# Handmouse.net
KiCad netlist of a schematic drawn in Altium Designer
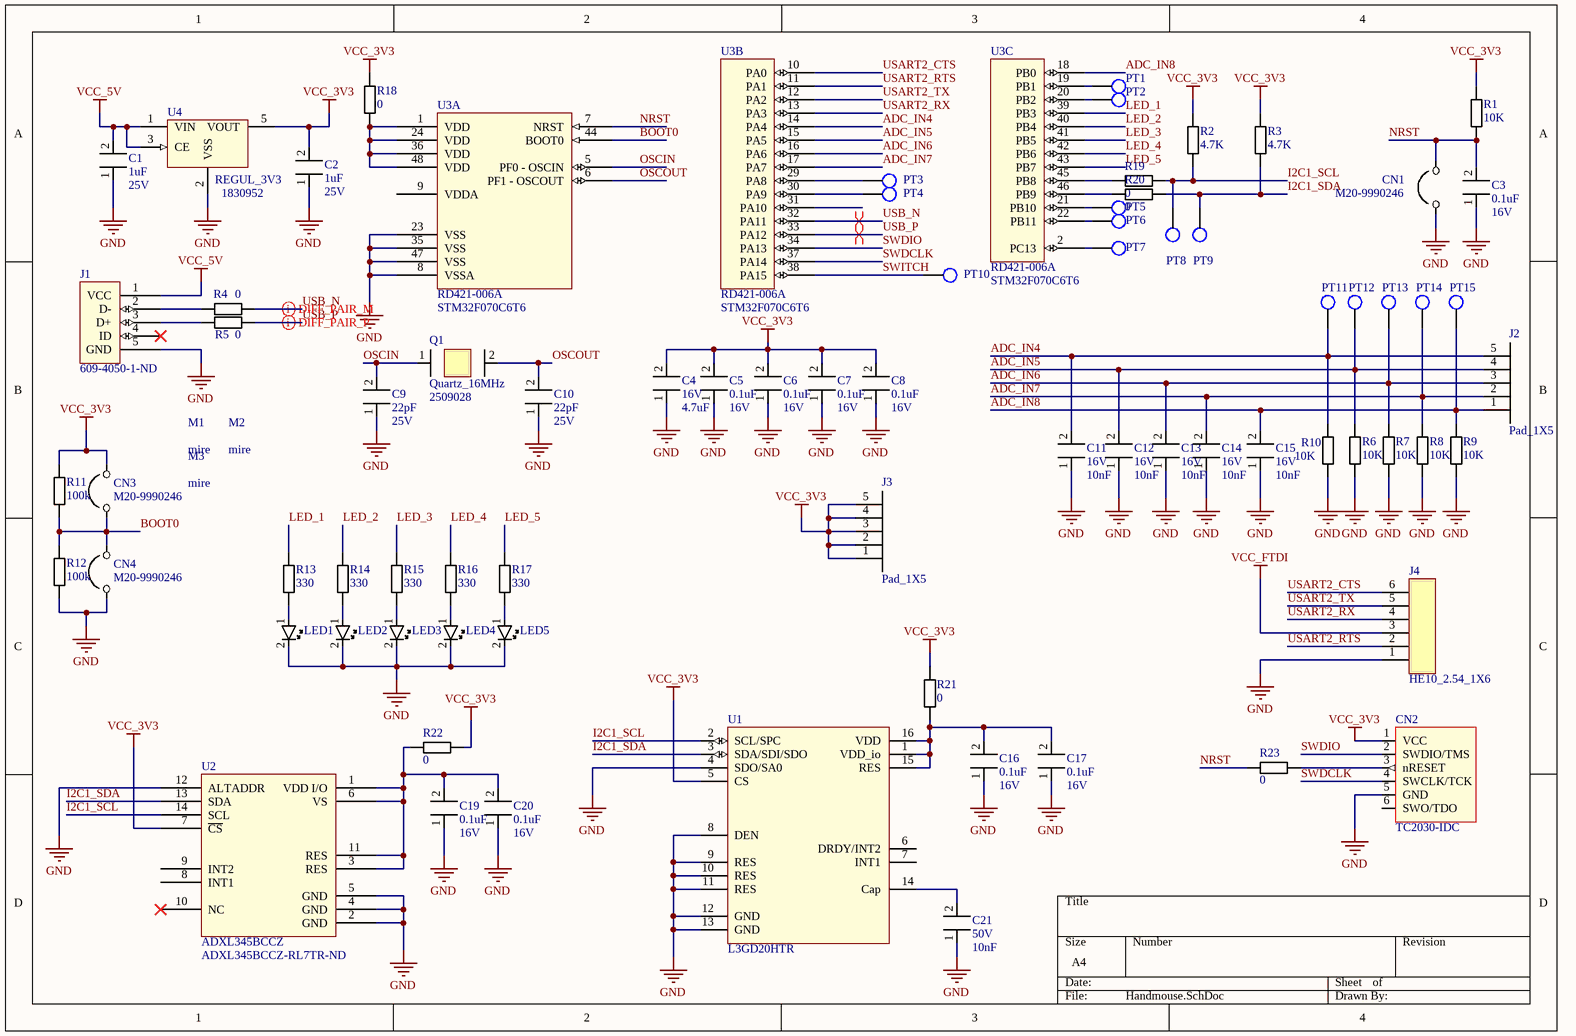
[diagram p0: Handmouse.SchDoc]

(export (version "E")
  (design (tool "Eeschema 10.0.6"))
  (components
    (comp (ref "C1")
      (value "RD401-021A")
      (footprint "0603")
      (description "CAP CER 0603 1uF 25V X7R 10%")
      (fields
        (field (name "MANUFACTURER") "AVX")
        (field (name "MANUFACTURER PART NUMBER") "0603YC105KAT2A")
        (field (name "CAPACITÉ") "1uF")
        (field (name "VOLTAGE") "25V")
      )
      (libsource (lib "Condensateur") (part "RD401-021A"))
    )
    (comp (ref "C2")
      (value "RD401-021A")
      (footprint "0603")
      (description "CAP CER 0603 1uF 25V X7R 10%")
      (fields
        (field (name "MANUFACTURER") "AVX")
        (field (name "MANUFACTURER PART NUMBER") "0603YC105KAT2A")
        (field (name "CAPACITÉ") "1uF")
        (field (name "VOLTAGE") "25V")
      )
      (libsource (lib "Condensateur") (part "RD401-021A"))
    )
    (comp (ref "C3")
      (value "RD401-033A")
      (footprint "0402")
      (description "CAP CER 0402 0.1uF 16V X7R 5%")
      (fields
        (field (name "MANUFACTURER") "KEMET")
        (field (name "MANUFACTURER PART NUMBER") "C0402C104J4RACTU")
        (field (name "CAPACITÉ") "0.1uF")
        (field (name "VOLTAGE") "16V")
      )
      (libsource (lib "Condensateur") (part "RD401-033A"))
    )
    (comp (ref "C4")
      (value "~")
      (footprint "0805")
      (description "CAP CER 0805 4.7uF 16V X7R 10%")
      (fields
        (field (name "MANUFACTURER") "AVX")
        (field (name "MANUFACTURER PART NUMBER") "0805YC475KAT2A")
        (field (name "VOLTAGE") "16V")
        (field (name "CAPACITÉ") "4.7uF")
      )
      (libsource (lib "Condensateur") (part "RD401-025A"))
    )
    (comp (ref "C5")
      (value "RD401-033A")
      (footprint "0402")
      (description "CAP CER 0402 0.1uF 16V X7R 5%")
      (fields
        (field (name "MANUFACTURER") "KEMET")
        (field (name "MANUFACTURER PART NUMBER") "C0402C104J4RACTU")
        (field (name "CAPACITÉ") "0.1uF")
        (field (name "VOLTAGE") "16V")
      )
      (libsource (lib "Condensateur") (part "RD401-033A"))
    )
    (comp (ref "C6")
      (value "RD401-033A")
      (footprint "0402")
      (description "CAP CER 0402 0.1uF 16V X7R 5%")
      (fields
        (field (name "MANUFACTURER") "KEMET")
        (field (name "MANUFACTURER PART NUMBER") "C0402C104J4RACTU")
        (field (name "CAPACITÉ") "0.1uF")
        (field (name "VOLTAGE") "16V")
      )
      (libsource (lib "Condensateur") (part "RD401-033A"))
    )
    (comp (ref "C7")
      (value "RD401-033A")
      (footprint "0402")
      (description "CAP CER 0402 0.1uF 16V X7R 5%")
      (fields
        (field (name "MANUFACTURER") "KEMET")
        (field (name "MANUFACTURER PART NUMBER") "C0402C104J4RACTU")
        (field (name "CAPACITÉ") "0.1uF")
        (field (name "VOLTAGE") "16V")
      )
      (libsource (lib "Condensateur") (part "RD401-033A"))
    )
    (comp (ref "C8")
      (value "RD401-033A")
      (footprint "0402")
      (description "CAP CER 0402 0.1uF 16V X7R 5%")
      (fields
        (field (name "MANUFACTURER") "KEMET")
        (field (name "MANUFACTURER PART NUMBER") "C0402C104J4RACTU")
        (field (name "CAPACITÉ") "0.1uF")
        (field (name "VOLTAGE") "16V")
      )
      (libsource (lib "Condensateur") (part "RD401-033A"))
    )
    (comp (ref "C9")
      (value "22pF")
      (footprint "0402")
      (description "CAP CER 0402 22pF 25V COG 1%")
      (fields (field (name "VOLTAGE") "25V"))
      (libsource (lib "Condensateur") (part "RD401-009A"))
    )
    (comp (ref "C10")
      (value "22pF")
      (footprint "0402")
      (description "CAP CER 0402 22pF 25V COG 1%")
      (fields (field (name "VOLTAGE") "25V"))
      (libsource (lib "Condensateur") (part "RD401-009A"))
    )
    (comp (ref "C11")
      (value "RD401-008A")
      (footprint "0402")
      (description "CAP CER 0402 10nF 16V X7R 5%")
      (fields (field (name "VOLTAGE") "16V") (field (name "CAPACITÉ") "10nF"))
      (libsource (lib "Condensateur") (part "RD401-008A"))
    )
    (comp (ref "C12")
      (value "RD401-008A")
      (footprint "0402")
      (description "CAP CER 0402 10nF 16V X7R 5%")
      (fields (field (name "VOLTAGE") "16V") (field (name "CAPACITÉ") "10nF"))
      (libsource (lib "Condensateur") (part "RD401-008A"))
    )
    (comp (ref "C13")
      (value "RD401-008A")
      (footprint "0402")
      (description "CAP CER 0402 10nF 16V X7R 5%")
      (fields (field (name "VOLTAGE") "16V") (field (name "CAPACITÉ") "10nF"))
      (libsource (lib "Condensateur") (part "RD401-008A"))
    )
    (comp (ref "C14")
      (value "RD401-008A")
      (footprint "0402")
      (description "CAP CER 0402 10nF 16V X7R 5%")
      (fields (field (name "VOLTAGE") "16V") (field (name "CAPACITÉ") "10nF"))
      (libsource (lib "Condensateur") (part "RD401-008A"))
    )
    (comp (ref "C15")
      (value "RD401-008A")
      (footprint "0402")
      (description "CAP CER 0402 10nF 16V X7R 5%")
      (fields (field (name "VOLTAGE") "16V") (field (name "CAPACITÉ") "10nF"))
      (libsource (lib "Condensateur") (part "RD401-008A"))
    )
    (comp (ref "C16")
      (value "RD401-033A")
      (footprint "0402")
      (description "CAP CER 0402 0.1uF 16V X7R 5%")
      (fields
        (field (name "MANUFACTURER") "KEMET")
        (field (name "MANUFACTURER PART NUMBER") "C0402C104J4RACTU")
        (field (name "CAPACITÉ") "0.1uF")
        (field (name "VOLTAGE") "16V")
      )
      (libsource (lib "Condensateur") (part "RD401-033A"))
    )
    (comp (ref "C17")
      (value "RD401-033A")
      (footprint "0402")
      (description "CAP CER 0402 0.1uF 16V X7R 5%")
      (fields
        (field (name "MANUFACTURER") "KEMET")
        (field (name "MANUFACTURER PART NUMBER") "C0402C104J4RACTU")
        (field (name "CAPACITÉ") "0.1uF")
        (field (name "VOLTAGE") "16V")
      )
      (libsource (lib "Condensateur") (part "RD401-033A"))
    )
    (comp (ref "C19")
      (value "RD401-033A")
      (footprint "0402")
      (description "CAP CER 0402 0.1uF 16V X7R 5%")
      (fields
        (field (name "MANUFACTURER") "KEMET")
        (field (name "MANUFACTURER PART NUMBER") "C0402C104J4RACTU")
        (field (name "CAPACITÉ") "0.1uF")
        (field (name "VOLTAGE") "16V")
      )
      (libsource (lib "Condensateur") (part "RD401-033A"))
    )
    (comp (ref "C20")
      (value "RD401-033A")
      (footprint "0402")
      (description "CAP CER 0402 0.1uF 16V X7R 5%")
      (fields
        (field (name "MANUFACTURER") "KEMET")
        (field (name "MANUFACTURER PART NUMBER") "C0402C104J4RACTU")
        (field (name "CAPACITÉ") "0.1uF")
        (field (name "VOLTAGE") "16V")
      )
      (libsource (lib "Condensateur") (part "RD401-033A"))
    )
    (comp (ref "C21")
      (value "RD401-037A")
      (footprint "0402")
      (description "CAP CER 0402 10nF 50V X7R 10%")
      (fields
        (field (name "MANUFACTURER") "KEMET")
        (field (name "MANUFACTURER PART NUMBER") "C0402C103K5RACTU")
        (field (name "VOLTAGE") "50V")
        (field (name "CAPACITE") "10nF")
      )
      (libsource (lib "Condensateur") (part "RD401-037A"))
    )
    (comp (ref "CN1")
      (value "RD408-013A")
      (footprint "PinHead 2*1 M")
      (description "JUMPER")
      (fields (field (name "MANUFACTURER PART NUMBER 1") "M20-9990246"))
      (libsource (lib "Connecteur") (part "RD408-013A"))
    )
    (comp (ref "CN2")
      (value "RD408-022A")
      (footprint "TC2030-IDC-FP")
      (description "CON SWD")
      (fields
        (field (name "MANUFACTURER") "Tag-Connect LLC")
        (field (name "MANUFACTURER PART NUMBER") "TC2030-IDC")
      )
      (libsource (lib "Connecteur") (part "RD408-022A"))
    )
    (comp (ref "CN3")
      (value "RD408-013A")
      (footprint "PinHead 2*1 M")
      (description "JUMPER")
      (fields (field (name "MANUFACTURER PART NUMBER 1") "M20-9990246"))
      (libsource (lib "Connecteur") (part "RD408-013A"))
    )
    (comp (ref "CN4")
      (value "RD408-013A")
      (footprint "PinHead 2*1 M")
      (description "JUMPER")
      (fields (field (name "MANUFACTURER PART NUMBER 1") "M20-9990246"))
      (libsource (lib "Connecteur") (part "RD408-013A"))
    )
    (comp (ref "J1")
      (value "CONN_FCI_10103594-0001LF")
      (footprint "CONN_10103594-0001LF")
      (description "CONN MICROUSB FCI 10103594-0001LF")
      (fields
        (field (name "MANUFACTURER") "Amphenol FCI")
        (field (name "MANUFACTURER PART NUMBER") "10103594-0001LF")
        (field (name "SUPPLIER PART NUMBER 1") "609-4050-1-ND")
      )
      (libsource (lib "Schlib1") (part "CONN_FCI_10103594-0001LF"))
    )
    (comp (ref "J2")
      (value "Pad_1X5")
      (footprint "PCBComponent_1")
      (libsource (lib "Schlib1") (part "Pad_1X5"))
    )
    (comp (ref "J3")
      (value "Pad_1X5")
      (footprint "PCBComponent_1")
      (libsource (lib "Schlib1") (part "Pad_1X5"))
    )
    (comp (ref "J4")
      (value "HE10_2.54_1X6")
      (footprint "PCBComponent_1 - duplicate")
      (libsource (lib "Schlib1") (part "HE10_2.54_1X6"))
    )
    (comp (ref "LED1")
      (value "RD405-006A")
      (footprint "0805")
      (description "DIO LED SMT ? 30mA Rouge")
      (libsource (lib "Diodes") (part "RD405-006A"))
    )
    (comp (ref "LED2")
      (value "RD405-006A")
      (footprint "0805")
      (description "DIO LED SMT ? 30mA Rouge")
      (libsource (lib "Diodes") (part "RD405-006A"))
    )
    (comp (ref "LED3")
      (value "RD405-006A")
      (footprint "0805")
      (description "DIO LED SMT ? 30mA Rouge")
      (libsource (lib "Diodes") (part "RD405-006A"))
    )
    (comp (ref "LED4")
      (value "RD405-006A")
      (footprint "0805")
      (description "DIO LED SMT ? 30mA Rouge")
      (libsource (lib "Diodes") (part "RD405-006A"))
    )
    (comp (ref "LED5")
      (value "RD405-006A")
      (footprint "0805")
      (description "DIO LED SMT ? 30mA Rouge")
      (libsource (lib "Diodes") (part "RD405-006A"))
    )
    (comp (ref "M1")
      (value "mire")
      (footprint "Miscellaneous:Mire")
      (libsource (lib "Miscellaneous") (part "mire"))
    )
    (comp (ref "M2")
      (value "mire")
      (footprint "Miscellaneous:Mire")
      (libsource (lib "Miscellaneous") (part "mire"))
    )
    (comp (ref "M3")
      (value "mire")
      (footprint "Miscellaneous:Mire")
      (libsource (lib "Miscellaneous") (part "mire"))
    )
    (comp (ref "PT1")
      (value "PT 0.8mm")
      (footprint "Pastille_0.8mm")
      (description "Point de test pastille 0.8mm")
      (libsource (lib "Schlib1") (part "PT 0.8mm"))
    )
    (comp (ref "PT2")
      (value "PT 0.8mm")
      (footprint "Pastille_0.8mm")
      (description "Point de test pastille 0.8mm")
      (libsource (lib "Schlib1") (part "PT 0.8mm"))
    )
    (comp (ref "PT3")
      (value "PT 0.8mm")
      (footprint "Pastille_0.8mm")
      (description "Point de test pastille 0.8mm")
      (libsource (lib "Schlib1") (part "PT 0.8mm"))
    )
    (comp (ref "PT4")
      (value "PT 0.8mm")
      (footprint "Pastille_0.8mm")
      (description "Point de test pastille 0.8mm")
      (libsource (lib "Schlib1") (part "PT 0.8mm"))
    )
    (comp (ref "PT5")
      (value "PT 0.8mm")
      (footprint "Pastille_0.8mm")
      (description "Point de test pastille 0.8mm")
      (libsource (lib "Schlib1") (part "PT 0.8mm"))
    )
    (comp (ref "PT6")
      (value "PT 0.8mm")
      (footprint "Pastille_0.8mm")
      (description "Point de test pastille 0.8mm")
      (libsource (lib "Schlib1") (part "PT 0.8mm"))
    )
    (comp (ref "PT7")
      (value "PT 0.8mm")
      (footprint "Pastille_0.8mm")
      (description "Point de test pastille 0.8mm")
      (libsource (lib "Schlib1") (part "PT 0.8mm"))
    )
    (comp (ref "PT8")
      (value "PT 0.8mm")
      (footprint "Pastille_0.8mm")
      (description "Point de test pastille 0.8mm")
      (libsource (lib "Schlib1") (part "PT 0.8mm"))
    )
    (comp (ref "PT9")
      (value "PT 0.8mm")
      (footprint "Pastille_0.8mm")
      (description "Point de test pastille 0.8mm")
      (libsource (lib "Schlib1") (part "PT 0.8mm"))
    )
    (comp (ref "PT10")
      (value "PT 0.8mm")
      (footprint "Pastille_0.8mm")
      (description "Point de test pastille 0.8mm")
      (libsource (lib "Schlib1") (part "PT 0.8mm"))
    )
    (comp (ref "PT11")
      (value "PT 0.8mm")
      (footprint "Pastille_0.8mm")
      (description "Point de test pastille 0.8mm")
      (libsource (lib "Schlib1") (part "PT 0.8mm"))
    )
    (comp (ref "PT12")
      (value "PT 0.8mm")
      (footprint "Pastille_0.8mm")
      (description "Point de test pastille 0.8mm")
      (libsource (lib "Schlib1") (part "PT 0.8mm"))
    )
    (comp (ref "PT13")
      (value "PT 0.8mm")
      (footprint "Pastille_0.8mm")
      (description "Point de test pastille 0.8mm")
      (libsource (lib "Schlib1") (part "PT 0.8mm"))
    )
    (comp (ref "PT14")
      (value "PT 0.8mm")
      (footprint "Pastille_0.8mm")
      (description "Point de test pastille 0.8mm")
      (libsource (lib "Schlib1") (part "PT 0.8mm"))
    )
    (comp (ref "PT15")
      (value "PT 0.8mm")
      (footprint "Pastille_0.8mm")
      (description "Point de test pastille 0.8mm")
      (libsource (lib "Schlib1") (part "PT 0.8mm"))
    )
    (comp (ref "Q1")
      (value "Quartz_16MHz")
      (footprint "PCBComponent_1 - duplicate2")
      (description "Quartz 16MHz")
      (fields
        (field (name "MANUFACTURER") "RALTRON")
        (field (name "MANUFACTURER PART NUMBER") "AS-16.000-18-SMD")
        (field (name "SUPPLIER PART NUMBER 1") "2509028")
      )
      (libsource (lib "Schlib1") (part "Quartz_16MHz"))
    )
    (comp (ref "R1")
      (value "RD403-054A")
      (footprint "0603")
      (description "RES 0603 10K 1% 0.1W")
      (fields
        (field (name "MANUFACTURER") "VISHAY DRALORIC")
        (field (name "MANUFACTURER PART NUMBER") "CRCW060310K0FKEA")
        (field (name "RESISTANCE") "10K")
      )
      (libsource (lib "Resistance") (part "RD403-054A"))
    )
    (comp (ref "R2")
      (value "RD403-046A")
      (footprint "0603")
      (description "RES 0603 4.7K 1% 0.1W")
      (fields
        (field (name "MANUFACTURER") "Vishay Dale")
        (field (name "MANUFACTURER PART NUMBER") "CRCW06034K70FKEA")
        (field (name "RÉSISTANCE (OHMS)") "4.7K")
        (field (name "HAUTEUR") "0,020 po (0,50 mm)")
      )
      (libsource (lib "Resistance") (part "RD403-046A"))
    )
    (comp (ref "R3")
      (value "RD403-046A")
      (footprint "0603")
      (description "RES 0603 4.7K 1% 0.1W")
      (fields
        (field (name "MANUFACTURER") "Vishay Dale")
        (field (name "MANUFACTURER PART NUMBER") "CRCW06034K70FKEA")
        (field (name "RÉSISTANCE (OHMS)") "4.7K")
        (field (name "HAUTEUR") "0,020 po (0,50 mm)")
      )
      (libsource (lib "Resistance") (part "RD403-046A"))
    )
    (comp (ref "R4")
      (value "RD403-044A")
      (footprint "0603")
      (description "RES 0603 0 1% 0.1W")
      (fields
        (field (name "MANUFACTURER") "VISHAY DRALORIC")
        (field (name "MANUFACTURER PART NUMBER") "CRCW06030000Z0EA")
        (field (name "RÉSISTANCE") "0")
      )
      (libsource (lib "Resistance") (part "RD403-044A"))
    )
    (comp (ref "R5")
      (value "RD403-044A")
      (footprint "0603")
      (description "RES 0603 0 1% 0.1W")
      (fields
        (field (name "MANUFACTURER") "VISHAY DRALORIC")
        (field (name "MANUFACTURER PART NUMBER") "CRCW06030000Z0EA")
        (field (name "RÉSISTANCE") "0")
      )
      (libsource (lib "Resistance") (part "RD403-044A"))
    )
    (comp (ref "R6")
      (value "RD403-054A")
      (footprint "0603")
      (description "RES 0603 10K 1% 0.1W")
      (fields
        (field (name "MANUFACTURER") "VISHAY DRALORIC")
        (field (name "MANUFACTURER PART NUMBER") "CRCW060310K0FKEA")
        (field (name "RESISTANCE") "10K")
      )
      (libsource (lib "Resistance") (part "RD403-054A"))
    )
    (comp (ref "R7")
      (value "RD403-054A")
      (footprint "0603")
      (description "RES 0603 10K 1% 0.1W")
      (fields
        (field (name "MANUFACTURER") "VISHAY DRALORIC")
        (field (name "MANUFACTURER PART NUMBER") "CRCW060310K0FKEA")
        (field (name "RESISTANCE") "10K")
      )
      (libsource (lib "Resistance") (part "RD403-054A"))
    )
    (comp (ref "R8")
      (value "RD403-054A")
      (footprint "0603")
      (description "RES 0603 10K 1% 0.1W")
      (fields
        (field (name "MANUFACTURER") "VISHAY DRALORIC")
        (field (name "MANUFACTURER PART NUMBER") "CRCW060310K0FKEA")
        (field (name "RESISTANCE") "10K")
      )
      (libsource (lib "Resistance") (part "RD403-054A"))
    )
    (comp (ref "R9")
      (value "RD403-054A")
      (footprint "0603")
      (description "RES 0603 10K 1% 0.1W")
      (fields
        (field (name "MANUFACTURER") "VISHAY DRALORIC")
        (field (name "MANUFACTURER PART NUMBER") "CRCW060310K0FKEA")
        (field (name "RESISTANCE") "10K")
      )
      (libsource (lib "Resistance") (part "RD403-054A"))
    )
    (comp (ref "R10")
      (value "RD403-054A")
      (footprint "0603")
      (description "RES 0603 10K 1% 0.1W")
      (fields
        (field (name "MANUFACTURER") "VISHAY DRALORIC")
        (field (name "MANUFACTURER PART NUMBER") "CRCW060310K0FKEA")
        (field (name "RESISTANCE") "10K")
      )
      (libsource (lib "Resistance") (part "RD403-054A"))
    )
    (comp (ref "R11")
      (value "100k")
      (footprint "0402")
      (description "RES 0402 100k 1% 0.063W")
      (libsource (lib "Resistance") (part "RD403-007A"))
    )
    (comp (ref "R12")
      (value "100k")
      (footprint "0402")
      (description "RES 0402 100k 1% 0.063W")
      (libsource (lib "Resistance") (part "RD403-007A"))
    )
    (comp (ref "R13")
      (value "330")
      (footprint "0402")
      (description "RES 0402 330 1% 0.063W")
      (libsource (lib "Resistance") (part "RD403-014A"))
    )
    (comp (ref "R14")
      (value "330")
      (footprint "0402")
      (description "RES 0402 330 1% 0.063W")
      (libsource (lib "Resistance") (part "RD403-014A"))
    )
    (comp (ref "R15")
      (value "330")
      (footprint "0402")
      (description "RES 0402 330 1% 0.063W")
      (libsource (lib "Resistance") (part "RD403-014A"))
    )
    (comp (ref "R16")
      (value "330")
      (footprint "0402")
      (description "RES 0402 330 1% 0.063W")
      (libsource (lib "Resistance") (part "RD403-014A"))
    )
    (comp (ref "R17")
      (value "330")
      (footprint "0402")
      (description "RES 0402 330 1% 0.063W")
      (libsource (lib "Resistance") (part "RD403-014A"))
    )
    (comp (ref "R18")
      (value "RD403-044A")
      (footprint "0603")
      (description "RES 0603 0 1% 0.1W")
      (fields
        (field (name "MANUFACTURER") "VISHAY DRALORIC")
        (field (name "MANUFACTURER PART NUMBER") "CRCW06030000Z0EA")
        (field (name "RÉSISTANCE") "0")
      )
      (libsource (lib "Resistance") (part "RD403-044A"))
    )
    (comp (ref "R19")
      (value "RD403-044A")
      (footprint "0603")
      (description "RES 0603 0 1% 0.1W")
      (fields
        (field (name "MANUFACTURER") "VISHAY DRALORIC")
        (field (name "MANUFACTURER PART NUMBER") "CRCW06030000Z0EA")
        (field (name "RÉSISTANCE") "0")
      )
      (libsource (lib "Resistance") (part "RD403-044A"))
    )
    (comp (ref "R20")
      (value "RD403-044A")
      (footprint "0603")
      (description "RES 0603 0 1% 0.1W")
      (fields
        (field (name "MANUFACTURER") "VISHAY DRALORIC")
        (field (name "MANUFACTURER PART NUMBER") "CRCW06030000Z0EA")
        (field (name "RÉSISTANCE") "0")
      )
      (libsource (lib "Resistance") (part "RD403-044A"))
    )
    (comp (ref "R21")
      (value "RD403-044A")
      (footprint "0603")
      (description "RES 0603 0 1% 0.1W")
      (fields
        (field (name "MANUFACTURER") "VISHAY DRALORIC")
        (field (name "MANUFACTURER PART NUMBER") "CRCW06030000Z0EA")
        (field (name "RÉSISTANCE") "0")
      )
      (libsource (lib "Resistance") (part "RD403-044A"))
    )
    (comp (ref "R22")
      (value "RD403-044A")
      (footprint "0603")
      (description "RES 0603 0 1% 0.1W")
      (fields
        (field (name "MANUFACTURER") "VISHAY DRALORIC")
        (field (name "MANUFACTURER PART NUMBER") "CRCW06030000Z0EA")
        (field (name "RÉSISTANCE") "0")
      )
      (libsource (lib "Resistance") (part "RD403-044A"))
    )
    (comp (ref "R23")
      (value "RD403-044A")
      (footprint "0603")
      (description "RES 0603 0 1% 0.1W")
      (fields
        (field (name "MANUFACTURER") "VISHAY DRALORIC")
        (field (name "MANUFACTURER PART NUMBER") "CRCW06030000Z0EA")
        (field (name "RÉSISTANCE") "0")
      )
      (libsource (lib "Resistance") (part "RD403-044A"))
    )
    (comp (ref "U1")
      (value "RD498-005A")
      (footprint "LGA_50P_300X300_16")
      (description "Gyroscopes MEMS motion sensor 3axis digital output")
      (fields (field (name "MANUFACTURER PART NUMBER 1") "L3GD20HTR") (field (name "HAUTEUR") "1 mm"))
      (libsource (lib "Miscellaneous") (part "RD498-005A"))
    )
    (comp (ref "U2")
      (value "ADXL345BCCZ")
      (footprint "PCBComponent_1 - duplicate1")
      (fields
        (field (name "MANUFACTURER") "Analog Devices Inc.")
        (field (name "MANUFACTURER PART NUMBER") "ADXL345BCCZ-RL7")
        (field (name "SUPPLIER PART NUMBER 1") "ADXL345BCCZ-RL7TR-ND")
      )
      (libsource (lib "Schlib1") (part "ADXL345BCCZ"))
    )
    (comp (ref "U3")
      (value "RD421-006A")
      (footprint "LQFP48")
      (description "STM32F070C6T6")
      (fields
        (field (name "MANUFACTURER") "STMICROELECTRONICS")
        (field (name "MANUFACTURER PART NUMBER") "STM32F070C6T6")
      )
      (libsource (lib "SOC") (part "RD421-006A"))
    )
    (comp (ref "U4")
      (value "REGUL_3V3")
      (footprint "SOIC95P280X130-5")
      (fields
        (field (name "MANUFACTURER") "TOREX")
        (field (name "MANUFACTURER PART NUMBER") "XC6222D331MR-G")
        (field (name "SUPPLIER PART NUMBER 1") "1830952")
      )
      (libsource (lib "Schlib1") (part "REGUL_3V3"))
    )
  )
  (nets
    (net (code "1") (name "/ADC_IN4") (class "Default")
      (node (ref "C11") (pin "2") (pinfunction "2_2") (pintype "passive"))
      (node (ref "J2") (pin "5") (pinfunction "5_5") (pintype "passive"))
      (node (ref "PT11") (pin "1") (pinfunction "1_1") (pintype "passive"))
      (node (ref "R10") (pin "2") (pinfunction "4_2") (pintype "passive"))
      (node (ref "U3") (pin "14") (pinfunction "PA4_14") (pintype "bidirectional"))
    )
    (net (code "2") (name "/ADC_IN5") (class "Default")
      (node (ref "C12") (pin "2") (pinfunction "2_2") (pintype "passive"))
      (node (ref "J2") (pin "4") (pinfunction "4_4") (pintype "passive"))
      (node (ref "PT12") (pin "1") (pinfunction "1_1") (pintype "passive"))
      (node (ref "R6") (pin "2") (pinfunction "4_2") (pintype "passive"))
      (node (ref "U3") (pin "15") (pinfunction "PA5_15") (pintype "bidirectional"))
    )
    (net (code "3") (name "/ADC_IN6") (class "Default")
      (node (ref "C13") (pin "2") (pinfunction "2_2") (pintype "passive"))
      (node (ref "J2") (pin "3") (pinfunction "3_3") (pintype "passive"))
      (node (ref "PT13") (pin "1") (pinfunction "1_1") (pintype "passive"))
      (node (ref "R7") (pin "2") (pinfunction "4_2") (pintype "passive"))
      (node (ref "U3") (pin "16") (pinfunction "PA6_16") (pintype "bidirectional"))
    )
    (net (code "4") (name "/ADC_IN7") (class "Default")
      (node (ref "C14") (pin "2") (pinfunction "2_2") (pintype "passive"))
      (node (ref "J2") (pin "2") (pinfunction "2_2") (pintype "passive"))
      (node (ref "PT14") (pin "1") (pinfunction "1_1") (pintype "passive"))
      (node (ref "R8") (pin "2") (pinfunction "4_2") (pintype "passive"))
      (node (ref "U3") (pin "17") (pinfunction "PA7_17") (pintype "bidirectional"))
    )
    (net (code "5") (name "/ADC_IN8") (class "Default")
      (node (ref "C15") (pin "2") (pinfunction "2_2") (pintype "passive"))
      (node (ref "J2") (pin "1") (pinfunction "1_1") (pintype "passive"))
      (node (ref "PT15") (pin "1") (pinfunction "1_1") (pintype "passive"))
      (node (ref "R9") (pin "2") (pinfunction "4_2") (pintype "passive"))
      (node (ref "U3") (pin "18") (pinfunction "PB0_18") (pintype "bidirectional"))
    )
    (net (code "6") (name "/BOOT0") (class "Default")
      (node (ref "CN3") (pin "1") (pinfunction "1_1") (pintype "power_in"))
      (node (ref "CN4") (pin "2") (pinfunction "2_2") (pintype "power_in"))
      (node (ref "R11") (pin "1") (pinfunction "3_1") (pintype "passive"))
      (node (ref "R12") (pin "2") (pinfunction "4_2") (pintype "passive"))
      (node (ref "U3") (pin "44") (pinfunction "BOOT0_44") (pintype "input"))
    )
    (net (code "7") (name "/I2C1_SCL") (class "Default")
      (node (ref "PT8") (pin "1") (pinfunction "1_1") (pintype "passive"))
      (node (ref "R19") (pin "2") (pinfunction "4_2") (pintype "passive"))
      (node (ref "R2") (pin "1") (pinfunction "3_1") (pintype "passive"))
      (node (ref "U1") (pin "2") (pinfunction "SCL/SPC_2") (pintype "bidirectional"))
      (node (ref "U2") (pin "14") (pinfunction "SCL_14") (pintype "passive"))
    )
    (net (code "8") (name "/I2C1_SDA") (class "Default")
      (node (ref "PT9") (pin "1") (pinfunction "1_1") (pintype "passive"))
      (node (ref "R20") (pin "2") (pinfunction "4_2") (pintype "passive"))
      (node (ref "R3") (pin "1") (pinfunction "3_1") (pintype "passive"))
      (node (ref "U1") (pin "3") (pinfunction "SDA/SDI/SDO_3") (pintype "bidirectional"))
      (node (ref "U2") (pin "13") (pinfunction "SDA_13") (pintype "passive"))
    )
    (net (code "9") (name "/LED_1") (class "Default")
      (node (ref "R13") (pin "2") (pinfunction "4_2") (pintype "passive"))
      (node (ref "U3") (pin "39") (pinfunction "PB3_39") (pintype "bidirectional"))
    )
    (net (code "10") (name "/LED_2") (class "Default")
      (node (ref "R14") (pin "2") (pinfunction "4_2") (pintype "passive"))
      (node (ref "U3") (pin "40") (pinfunction "PB4_40") (pintype "bidirectional"))
    )
    (net (code "11") (name "/LED_3") (class "Default")
      (node (ref "R15") (pin "2") (pinfunction "4_2") (pintype "passive"))
      (node (ref "U3") (pin "41") (pinfunction "PB5_41") (pintype "bidirectional"))
    )
    (net (code "12") (name "/LED_4") (class "Default")
      (node (ref "R16") (pin "2") (pinfunction "4_2") (pintype "passive"))
      (node (ref "U3") (pin "42") (pinfunction "PB6_42") (pintype "bidirectional"))
    )
    (net (code "13") (name "/LED_5") (class "Default")
      (node (ref "R17") (pin "2") (pinfunction "4_2") (pintype "passive"))
      (node (ref "U3") (pin "43") (pinfunction "PB7_43") (pintype "bidirectional"))
    )
    (net (code "14") (name "/NRST") (class "Default")
      (node (ref "C3") (pin "2") (pinfunction "2_2") (pintype "passive"))
      (node (ref "CN1") (pin "2") (pinfunction "2_2") (pintype "power_in"))
      (node (ref "R1") (pin "1") (pinfunction "3_1") (pintype "passive"))
      (node (ref "R23") (pin "2") (pinfunction "4_2") (pintype "passive"))
      (node (ref "U3") (pin "7") (pinfunction "NRST_7") (pintype "input"))
    )
    (net (code "15") (name "/OSCIN") (class "Default")
      (node (ref "C9") (pin "2") (pinfunction "2_2") (pintype "passive"))
      (node (ref "Q1") (pin "1") (pinfunction "1_1") (pintype "passive"))
      (node (ref "U3") (pin "5") (pinfunction "PF0_-_OSCIN_5") (pintype "bidirectional"))
    )
    (net (code "16") (name "/OSCOUT") (class "Default")
      (node (ref "C10") (pin "2") (pinfunction "2_2") (pintype "passive"))
      (node (ref "Q1") (pin "2") (pinfunction "2_2") (pintype "passive"))
      (node (ref "U3") (pin "6") (pinfunction "PF1_-_OSCOUT_6") (pintype "bidirectional"))
    )
    (net (code "17") (name "/SWDCLK") (class "Default")
      (node (ref "CN2") (pin "4") (pinfunction "SWCLK/TCK_4") (pintype "bidirectional"))
      (node (ref "U3") (pin "37") (pinfunction "PA14_37") (pintype "bidirectional"))
    )
    (net (code "18") (name "/SWDIO") (class "Default")
      (node (ref "CN2") (pin "2") (pinfunction "SWDIO/TMS_2") (pintype "bidirectional"))
      (node (ref "U3") (pin "34") (pinfunction "PA13_34") (pintype "bidirectional"))
    )
    (net (code "19") (name "/SWITCH") (class "Default")
      (node (ref "PT10") (pin "1") (pinfunction "1_1") (pintype "passive"))
      (node (ref "U3") (pin "38") (pinfunction "PA15_38") (pintype "bidirectional"))
    )
    (net (code "20") (name "/USART2_CTS") (class "Default")
      (node (ref "J4") (pin "6") (pinfunction "6_6") (pintype "passive"))
      (node (ref "U3") (pin "10") (pinfunction "PA0_10") (pintype "bidirectional"))
    )
    (net (code "21") (name "/USART2_RTS") (class "Default")
      (node (ref "J4") (pin "2") (pinfunction "2_2") (pintype "passive"))
      (node (ref "U3") (pin "11") (pinfunction "PA1_11") (pintype "bidirectional"))
    )
    (net (code "22") (name "/USART2_RX") (class "Default")
      (node (ref "J4") (pin "4") (pinfunction "4_4") (pintype "passive"))
      (node (ref "U3") (pin "13") (pinfunction "PA3_13") (pintype "bidirectional"))
    )
    (net (code "23") (name "/USART2_TX") (class "Default")
      (node (ref "J4") (pin "5") (pinfunction "5_5") (pintype "passive"))
      (node (ref "U3") (pin "12") (pinfunction "PA2_12") (pintype "bidirectional"))
    )
    (net (code "24") (name "/USB_N") (class "Default")
      (node (ref "R4") (pin "2") (pinfunction "4_2") (pintype "passive"))
      (node (ref "U3") (pin "32") (pinfunction "PA11_32") (pintype "bidirectional"))
    )
    (net (code "25") (name "/USB_P") (class "Default")
      (node (ref "R5") (pin "2") (pinfunction "4_2") (pintype "passive"))
      (node (ref "U3") (pin "33") (pinfunction "PA12_33") (pintype "bidirectional"))
    )
    (net (code "26") (name "GND") (class "Default")
      (node (ref "C1") (pin "1") (pinfunction "1_1") (pintype "passive"))
      (node (ref "C10") (pin "1") (pinfunction "1_1") (pintype "passive"))
      (node (ref "C11") (pin "1") (pinfunction "1_1") (pintype "passive"))
      (node (ref "C12") (pin "1") (pinfunction "1_1") (pintype "passive"))
      (node (ref "C13") (pin "1") (pinfunction "1_1") (pintype "passive"))
      (node (ref "C14") (pin "1") (pinfunction "1_1") (pintype "passive"))
      (node (ref "C15") (pin "1") (pinfunction "1_1") (pintype "passive"))
      (node (ref "C16") (pin "1") (pinfunction "1_1") (pintype "passive"))
      (node (ref "C17") (pin "1") (pinfunction "1_1") (pintype "passive"))
      (node (ref "C19") (pin "1") (pinfunction "1_1") (pintype "passive"))
      (node (ref "C2") (pin "1") (pinfunction "1_1") (pintype "passive"))
      (node (ref "C20") (pin "1") (pinfunction "1_1") (pintype "passive"))
      (node (ref "C21") (pin "1") (pinfunction "1_1") (pintype "passive"))
      (node (ref "C3") (pin "1") (pinfunction "1_1") (pintype "passive"))
      (node (ref "C4") (pin "1") (pinfunction "1_1") (pintype "passive"))
      (node (ref "C5") (pin "1") (pinfunction "1_1") (pintype "passive"))
      (node (ref "C6") (pin "1") (pinfunction "1_1") (pintype "passive"))
      (node (ref "C7") (pin "1") (pinfunction "1_1") (pintype "passive"))
      (node (ref "C8") (pin "1") (pinfunction "1_1") (pintype "passive"))
      (node (ref "C9") (pin "1") (pinfunction "1_1") (pintype "passive"))
      (node (ref "CN1") (pin "1") (pinfunction "1_1") (pintype "power_in"))
      (node (ref "CN2") (pin "5") (pinfunction "GND_5") (pintype "power_in"))
      (node (ref "CN4") (pin "1") (pinfunction "1_1") (pintype "power_in"))
      (node (ref "J1") (pin "5") (pinfunction "GND_5") (pintype "power_in"))
      (node (ref "J4") (pin "1") (pinfunction "1_1") (pintype "passive"))
      (node (ref "LED1") (pin "2") (pinfunction "2_2") (pintype "passive"))
      (node (ref "LED2") (pin "2") (pinfunction "2_2") (pintype "passive"))
      (node (ref "LED3") (pin "2") (pinfunction "2_2") (pintype "passive"))
      (node (ref "LED4") (pin "2") (pinfunction "2_2") (pintype "passive"))
      (node (ref "LED5") (pin "2") (pinfunction "2_2") (pintype "passive"))
      (node (ref "R10") (pin "1") (pinfunction "3_1") (pintype "passive"))
      (node (ref "R12") (pin "1") (pinfunction "3_1") (pintype "passive"))
      (node (ref "R6") (pin "1") (pinfunction "3_1") (pintype "passive"))
      (node (ref "R7") (pin "1") (pinfunction "3_1") (pintype "passive"))
      (node (ref "R8") (pin "1") (pinfunction "3_1") (pintype "passive"))
      (node (ref "R9") (pin "1") (pinfunction "3_1") (pintype "passive"))
      (node (ref "U1") (pin "10") (pinfunction "RES_10") (pintype "passive"))
      (node (ref "U1") (pin "11") (pinfunction "RES_11") (pintype "passive"))
      (node (ref "U1") (pin "12") (pinfunction "GND_12") (pintype "power_in"))
      (node (ref "U1") (pin "13") (pinfunction "GND_13") (pintype "power_in"))
      (node (ref "U1") (pin "4") (pinfunction "SDO/SA0_4") (pintype "passive"))
      (node (ref "U1") (pin "8") (pinfunction "DEN_8") (pintype "passive"))
      (node (ref "U1") (pin "9") (pinfunction "RES_9") (pintype "passive"))
      (node (ref "U2") (pin "12") (pinfunction "ALTADDR_12") (pintype "passive"))
      (node (ref "U2") (pin "2") (pinfunction "GND_2") (pintype "power_in"))
      (node (ref "U2") (pin "4") (pinfunction "GND_4") (pintype "power_in"))
      (node (ref "U2") (pin "5") (pinfunction "GND_5") (pintype "power_in"))
      (node (ref "U3") (pin "23") (pinfunction "VSS_23") (pintype "power_in"))
      (node (ref "U3") (pin "35") (pinfunction "VSS_35") (pintype "power_in"))
      (node (ref "U3") (pin "47") (pinfunction "VSS_47") (pintype "power_in"))
      (node (ref "U3") (pin "8") (pinfunction "VSSA_8") (pintype "power_in"))
      (node (ref "U4") (pin "2") (pinfunction "VSS_2") (pintype "power_in"))
    )
    (net (code "27") (name "Net-(CN2-nRESET)") (class "Default")
      (node (ref "CN2") (pin "3") (pinfunction "nRESET_3") (pintype "output"))
      (node (ref "R23") (pin "1") (pinfunction "3_1") (pintype "passive"))
    )
    (net (code "28") (name "Net-(J1-D+)") (class "Default")
      (node (ref "J1") (pin "3") (pinfunction "D+_3") (pintype "bidirectional"))
      (node (ref "R5") (pin "1") (pinfunction "3_1") (pintype "passive"))
    )
    (net (code "29") (name "Net-(J1-D-)") (class "Default")
      (node (ref "J1") (pin "2") (pinfunction "D-_2") (pintype "bidirectional"))
      (node (ref "R4") (pin "1") (pinfunction "3_1") (pintype "passive"))
    )
    (net (code "30") (name "Net-(R13-3)") (class "Default")
      (node (ref "LED1") (pin "1") (pinfunction "1_1") (pintype "passive"))
      (node (ref "R13") (pin "1") (pinfunction "3_1") (pintype "passive"))
    )
    (net (code "31") (name "Net-(R14-3)") (class "Default")
      (node (ref "LED2") (pin "1") (pinfunction "1_1") (pintype "passive"))
      (node (ref "R14") (pin "1") (pinfunction "3_1") (pintype "passive"))
    )
    (net (code "32") (name "Net-(R15-3)") (class "Default")
      (node (ref "LED3") (pin "1") (pinfunction "1_1") (pintype "passive"))
      (node (ref "R15") (pin "1") (pinfunction "3_1") (pintype "passive"))
    )
    (net (code "33") (name "Net-(R16-3)") (class "Default")
      (node (ref "LED4") (pin "1") (pinfunction "1_1") (pintype "passive"))
      (node (ref "R16") (pin "1") (pinfunction "3_1") (pintype "passive"))
    )
    (net (code "34") (name "Net-(R17-3)") (class "Default")
      (node (ref "LED5") (pin "1") (pinfunction "1_1") (pintype "passive"))
      (node (ref "R17") (pin "1") (pinfunction "3_1") (pintype "passive"))
    )
    (net (code "35") (name "Net-(R18-3)") (class "Default")
      (node (ref "R18") (pin "1") (pinfunction "3_1") (pintype "passive"))
      (node (ref "U3") (pin "1") (pinfunction "VDD_1") (pintype "passive"))
      (node (ref "U3") (pin "24") (pinfunction "VDD_24") (pintype "power_in"))
      (node (ref "U3") (pin "36") (pinfunction "VDD_36") (pintype "power_in"))
      (node (ref "U3") (pin "48") (pinfunction "VDD_48") (pintype "power_in"))
    )
    (net (code "36") (name "Net-(R19-3)") (class "Default")
      (node (ref "R19") (pin "1") (pinfunction "3_1") (pintype "passive"))
      (node (ref "U3") (pin "45") (pinfunction "PB8_45") (pintype "bidirectional"))
    )
    (net (code "37") (name "Net-(R20-3)") (class "Default")
      (node (ref "R20") (pin "1") (pinfunction "3_1") (pintype "passive"))
      (node (ref "U3") (pin "46") (pinfunction "PB9_46") (pintype "bidirectional"))
    )
    (net (code "38") (name "Net-(R21-3)") (class "Default")
      (node (ref "C16") (pin "2") (pinfunction "2_2") (pintype "passive"))
      (node (ref "C17") (pin "2") (pinfunction "2_2") (pintype "passive"))
      (node (ref "R21") (pin "1") (pinfunction "3_1") (pintype "passive"))
      (node (ref "U1") (pin "1") (pinfunction "VDD_io_1") (pintype "power_in"))
      (node (ref "U1") (pin "15") (pinfunction "RES_15") (pintype "passive"))
      (node (ref "U1") (pin "16") (pinfunction "VDD_16") (pintype "power_in"))
    )
    (net (code "39") (name "Net-(R22-3)") (class "Default")
      (node (ref "C19") (pin "2") (pinfunction "2_2") (pintype "passive"))
      (node (ref "C20") (pin "2") (pinfunction "2_2") (pintype "passive"))
      (node (ref "R22") (pin "1") (pinfunction "3_1") (pintype "passive"))
      (node (ref "U2") (pin "1") (pinfunction "VDD_I/O_1") (pintype "power_in"))
      (node (ref "U2") (pin "11") (pinfunction "RES_11") (pintype "passive"))
      (node (ref "U2") (pin "3") (pinfunction "RES_3") (pintype "power_in"))
      (node (ref "U2") (pin "6") (pinfunction "VS_6") (pintype "power_in"))
    )
    (net (code "40") (name "Net-(U1-Cap)") (class "Default")
      (node (ref "C21") (pin "2") (pinfunction "2_2") (pintype "passive"))
      (node (ref "U1") (pin "14") (pinfunction "Cap_14") (pintype "passive"))
    )
    (net (code "41") (name "Net-(U3B-PA8)") (class "Default")
      (node (ref "PT3") (pin "1") (pinfunction "1_1") (pintype "passive"))
      (node (ref "U3") (pin "29") (pinfunction "PA8_29") (pintype "bidirectional"))
    )
    (net (code "42") (name "Net-(U3B-PA9)") (class "Default")
      (node (ref "PT4") (pin "1") (pinfunction "1_1") (pintype "passive"))
      (node (ref "U3") (pin "30") (pinfunction "PA9_30") (pintype "bidirectional"))
    )
    (net (code "43") (name "Net-(U3C-PB1)") (class "Default")
      (node (ref "PT1") (pin "1") (pinfunction "1_1") (pintype "passive"))
      (node (ref "U3") (pin "19") (pinfunction "PB1_19") (pintype "bidirectional"))
    )
    (net (code "44") (name "Net-(U3C-PB2)") (class "Default")
      (node (ref "PT2") (pin "1") (pinfunction "1_1") (pintype "passive"))
      (node (ref "U3") (pin "20") (pinfunction "PB2_20") (pintype "bidirectional"))
    )
    (net (code "45") (name "Net-(U3C-PB10)") (class "Default")
      (node (ref "PT5") (pin "1") (pinfunction "1_1") (pintype "passive"))
      (node (ref "U3") (pin "21") (pinfunction "PB10_21") (pintype "bidirectional"))
    )
    (net (code "46") (name "Net-(U3C-PB11)") (class "Default")
      (node (ref "PT6") (pin "1") (pinfunction "1_1") (pintype "passive"))
      (node (ref "U3") (pin "22") (pinfunction "PB11_22") (pintype "bidirectional"))
    )
    (net (code "47") (name "Net-(U3C-PC13)") (class "Default")
      (node (ref "PT7") (pin "1") (pinfunction "1_1") (pintype "passive"))
      (node (ref "U3") (pin "2") (pinfunction "PC13_2") (pintype "bidirectional"))
    )
    (net (code "48") (name "VCC_3V3") (class "Default")
      (node (ref "C2") (pin "2") (pinfunction "2_2") (pintype "passive"))
      (node (ref "C4") (pin "2") (pinfunction "2_2") (pintype "passive"))
      (node (ref "C5") (pin "2") (pinfunction "2_2") (pintype "passive"))
      (node (ref "C6") (pin "2") (pinfunction "2_2") (pintype "passive"))
      (node (ref "C7") (pin "2") (pinfunction "2_2") (pintype "passive"))
      (node (ref "C8") (pin "2") (pinfunction "2_2") (pintype "passive"))
      (node (ref "CN2") (pin "1") (pinfunction "VCC_1") (pintype "power_in"))
      (node (ref "CN3") (pin "2") (pinfunction "2_2") (pintype "power_in"))
      (node (ref "J3") (pin "1") (pinfunction "1_1") (pintype "passive"))
      (node (ref "J3") (pin "2") (pinfunction "2_2") (pintype "passive"))
      (node (ref "J3") (pin "3") (pinfunction "3_3") (pintype "passive"))
      (node (ref "J3") (pin "4") (pinfunction "4_4") (pintype "passive"))
      (node (ref "J3") (pin "5") (pinfunction "5_5") (pintype "passive"))
      (node (ref "R1") (pin "2") (pinfunction "4_2") (pintype "passive"))
      (node (ref "R11") (pin "2") (pinfunction "4_2") (pintype "passive"))
      (node (ref "R18") (pin "2") (pinfunction "4_2") (pintype "passive"))
      (node (ref "R2") (pin "2") (pinfunction "4_2") (pintype "passive"))
      (node (ref "R21") (pin "2") (pinfunction "4_2") (pintype "passive"))
      (node (ref "R22") (pin "2") (pinfunction "4_2") (pintype "passive"))
      (node (ref "R3") (pin "2") (pinfunction "4_2") (pintype "passive"))
      (node (ref "U1") (pin "5") (pinfunction "CS_5") (pintype "passive"))
      (node (ref "U2") (pin "7") (pinfunction "~{CS}_7") (pintype "power_in"))
      (node (ref "U4") (pin "5") (pinfunction "VOUT_5") (pintype "power_in"))
    )
    (net (code "49") (name "VCC_5V") (class "Default")
      (node (ref "C1") (pin "2") (pinfunction "2_2") (pintype "passive"))
      (node (ref "J1") (pin "1") (pinfunction "VCC_1") (pintype "power_in"))
      (node (ref "U4") (pin "1") (pinfunction "VIN_1") (pintype "power_in"))
      (node (ref "U4") (pin "3") (pinfunction "CE_3") (pintype "input"))
    )
    (net (code "50") (name "VCC_FTDI") (class "Default")
      (node (ref "J4") (pin "3") (pinfunction "3_3") (pintype "passive"))
    )
    (net (code "51") (name "unconnected-(CN2-SWO{slash}TDO-Pad6)") (class "Default")
      (node (ref "CN2") (pin "6") (pinfunction "SWO/TDO_6") (pintype "bidirectional"))
    )
    (net (code "52") (name "unconnected-(J1-ID-Pad4)") (class "Default")
      (node (ref "J1") (pin "4") (pinfunction "ID_4") (pintype "bidirectional+no_connect"))
    )
    (net (code "53") (name "unconnected-(U1-DRDY{slash}INT2-Pad6)") (class "Default")
      (node (ref "U1") (pin "6") (pinfunction "DRDY/INT2_6") (pintype "passive"))
    )
    (net (code "54") (name "unconnected-(U1-INT1-Pad7)") (class "Default")
      (node (ref "U1") (pin "7") (pinfunction "INT1_7") (pintype "passive"))
    )
    (net (code "55") (name "unconnected-(U2-INT1-Pad8)") (class "Default")
      (node (ref "U2") (pin "8") (pinfunction "INT1_8") (pintype "power_in"))
    )
    (net (code "56") (name "unconnected-(U2-INT2-Pad9)") (class "Default")
      (node (ref "U2") (pin "9") (pinfunction "INT2_9") (pintype "power_in"))
    )
    (net (code "57") (name "unconnected-(U2-NC-Pad10)") (class "Default")
      (node (ref "U2") (pin "10") (pinfunction "NC_10") (pintype "passive+no_connect"))
    )
    (net (code "58") (name "unconnected-(U3A-VDDA-Pad9)") (class "Default")
      (node (ref "U3") (pin "9") (pinfunction "VDDA_9") (pintype "power_in"))
    )
    (net (code "59") (name "unconnected-(U3B-PA10-Pad31)") (class "Default")
      (node (ref "U3") (pin "31") (pinfunction "PA10_31") (pintype "bidirectional"))
    )
    (net (code "60") (name "unconnected-(U4-NC-Pad4)") (class "Default")
      (node (ref "U4") (pin "4") (pinfunction "NC_4") (pintype "passive"))
    )
  )
)
